# PotDiv2_v2.net
KiCad netlist of a schematic drawn in EAGLE
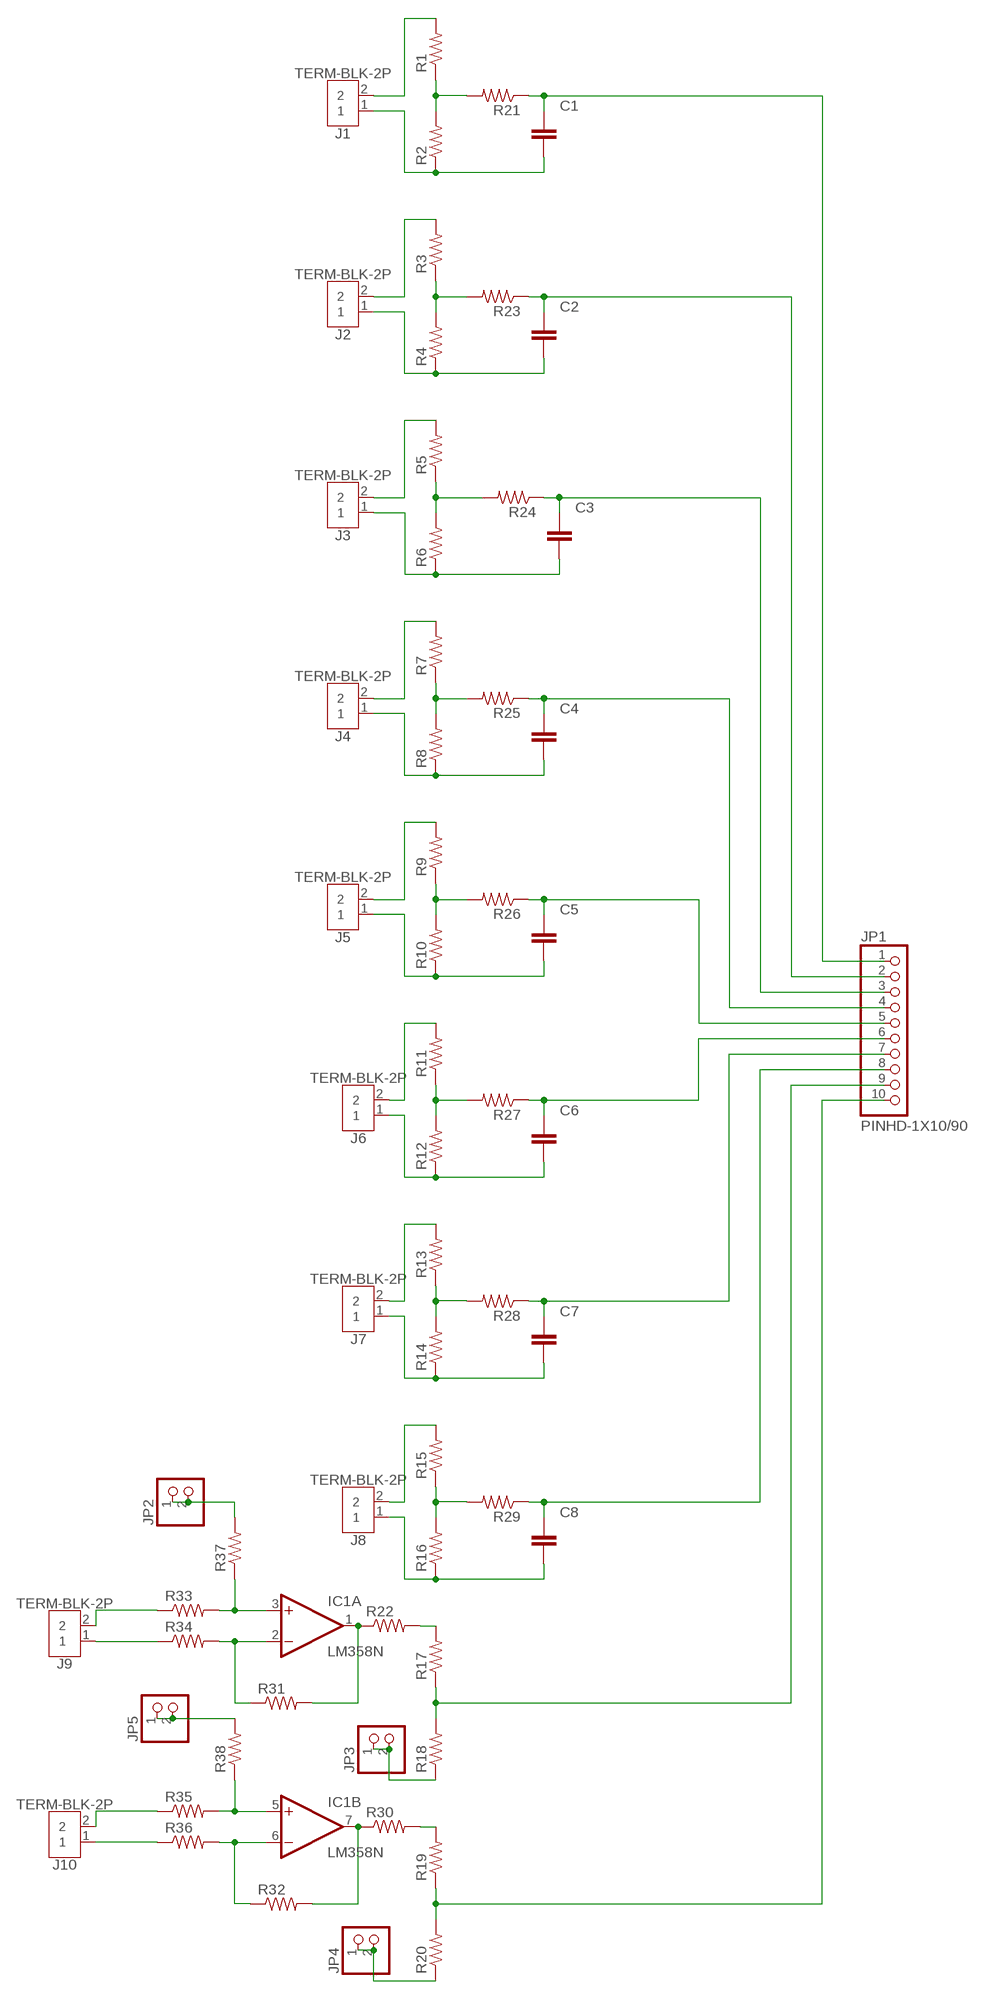
[diagram p0: schematic, sheet 1]

(export (version "E")
  (design (tool "Eeschema 10.0.6"))
  (components
    (comp (ref "C1")
      (value "C_RADIAL-12.5MM-DIA")
      (footprint "eagle-import:CAPRD550W60D1025H1250B")
      (libsource (lib "eagle-import") (part "CRADIAL-12.5MM-DIA_"))
    )
    (comp (ref "C2")
      (value "C_RADIAL-12.5MM-DIA")
      (footprint "eagle-import:CAPRD550W60D1025H1250B")
      (libsource (lib "eagle-import") (part "CRADIAL-12.5MM-DIA_"))
    )
    (comp (ref "C3")
      (value "C_RADIAL-12.5MM-DIA")
      (footprint "eagle-import:CAPRD550W60D1025H1250B")
      (libsource (lib "eagle-import") (part "CRADIAL-12.5MM-DIA_"))
    )
    (comp (ref "C4")
      (value "C_RADIAL-12.5MM-DIA")
      (footprint "eagle-import:CAPRD550W60D1025H1250B")
      (libsource (lib "eagle-import") (part "CRADIAL-12.5MM-DIA_"))
    )
    (comp (ref "C5")
      (value "C_RADIAL-12.5MM-DIA")
      (footprint "eagle-import:CAPRD550W60D1025H1250B")
      (libsource (lib "eagle-import") (part "CRADIAL-12.5MM-DIA_"))
    )
    (comp (ref "C6")
      (value "C_RADIAL-12.5MM-DIA")
      (footprint "eagle-import:CAPRD550W60D1025H1250B")
      (libsource (lib "eagle-import") (part "CRADIAL-12.5MM-DIA_"))
    )
    (comp (ref "C7")
      (value "C_RADIAL-12.5MM-DIA")
      (footprint "eagle-import:CAPRD550W60D1025H1250B")
      (libsource (lib "eagle-import") (part "CRADIAL-12.5MM-DIA_"))
    )
    (comp (ref "C8")
      (value "C_RADIAL-12.5MM-DIA")
      (footprint "eagle-import:CAPRD550W60D1025H1250B")
      (libsource (lib "eagle-import") (part "CRADIAL-12.5MM-DIA_"))
    )
    (comp (ref "IC1")
      (value "LM358N")
      (footprint "eagle-import:DIL08")
      (libsource (lib "eagle-import") (part "LM358N"))
    )
    (comp (ref "J1")
      (value "TERM-BLK-2P")
      (footprint "eagle-import:TERMBLK_508-2N")
      (fields (field (name "MANUFACTURER") "TE Connectivity AMP Connectors") (field (name "MPN") "282837-2"))
      (libsource (lib "eagle-import") (part "2828XX-2282837-2"))
    )
    (comp (ref "J2")
      (value "TERM-BLK-2P")
      (footprint "eagle-import:TERMBLK_508-2N")
      (fields (field (name "MANUFACTURER") "TE Connectivity AMP Connectors") (field (name "MPN") "282837-2"))
      (libsource (lib "eagle-import") (part "2828XX-2282837-2"))
    )
    (comp (ref "J3")
      (value "TERM-BLK-2P")
      (footprint "eagle-import:TERMBLK_508-2N")
      (fields (field (name "MANUFACTURER") "TE Connectivity AMP Connectors") (field (name "MPN") "282837-2"))
      (libsource (lib "eagle-import") (part "2828XX-2282837-2"))
    )
    (comp (ref "J4")
      (value "TERM-BLK-2P")
      (footprint "eagle-import:TERMBLK_508-2N")
      (fields (field (name "MANUFACTURER") "TE Connectivity AMP Connectors") (field (name "MPN") "282837-2"))
      (libsource (lib "eagle-import") (part "2828XX-2282837-2"))
    )
    (comp (ref "J5")
      (value "TERM-BLK-2P")
      (footprint "eagle-import:TERMBLK_508-2N")
      (fields (field (name "MANUFACTURER") "TE Connectivity AMP Connectors") (field (name "MPN") "282837-2"))
      (libsource (lib "eagle-import") (part "2828XX-2282837-2"))
    )
    (comp (ref "J6")
      (value "TERM-BLK-2P")
      (footprint "eagle-import:TERMBLK_508-2N")
      (fields (field (name "MANUFACTURER") "TE Connectivity AMP Connectors") (field (name "MPN") "282837-2"))
      (libsource (lib "eagle-import") (part "2828XX-2282837-2"))
    )
    (comp (ref "J7")
      (value "TERM-BLK-2P")
      (footprint "eagle-import:TERMBLK_508-2N")
      (fields (field (name "MANUFACTURER") "TE Connectivity AMP Connectors") (field (name "MPN") "282837-2"))
      (libsource (lib "eagle-import") (part "2828XX-2282837-2"))
    )
    (comp (ref "J8")
      (value "TERM-BLK-2P")
      (footprint "eagle-import:TERMBLK_508-2N")
      (fields (field (name "MANUFACTURER") "TE Connectivity AMP Connectors") (field (name "MPN") "282837-2"))
      (libsource (lib "eagle-import") (part "2828XX-2282837-2"))
    )
    (comp (ref "J9")
      (value "TERM-BLK-2P")
      (footprint "eagle-import:TERMBLK_508-2N")
      (fields (field (name "MANUFACTURER") "TE Connectivity AMP Connectors") (field (name "MPN") "282837-2"))
      (libsource (lib "eagle-import") (part "2828XX-2282837-2"))
    )
    (comp (ref "J10")
      (value "TERM-BLK-2P")
      (footprint "eagle-import:TERMBLK_508-2N")
      (fields (field (name "MANUFACTURER") "TE Connectivity AMP Connectors") (field (name "MPN") "282837-2"))
      (libsource (lib "eagle-import") (part "2828XX-2282837-2"))
    )
    (comp (ref "JP1")
      (value "PINHD-1X10/90")
      (footprint "eagle-import:1X10_90")
      (fields (field (name "MANUFACTURER") "Generic"))
      (libsource (lib "eagle-import") (part "PINHD-1X10/90"))
    )
    (comp (ref "JP2")
      (value "PINHD-1X2")
      (footprint "eagle-import:1X02")
      (libsource (lib "eagle-import") (part "PINHD-1X2"))
    )
    (comp (ref "JP3")
      (value "PINHD-1X2")
      (footprint "eagle-import:1X02")
      (libsource (lib "eagle-import") (part "PINHD-1X2"))
    )
    (comp (ref "JP4")
      (value "PINHD-1X2")
      (footprint "eagle-import:1X02")
      (libsource (lib "eagle-import") (part "PINHD-1X2"))
    )
    (comp (ref "JP5")
      (value "PINHD-1X2")
      (footprint "eagle-import:1X02")
      (libsource (lib "eagle-import") (part "PINHD-1X2"))
    )
    (comp (ref "R1")
      (value "R-US_AXIAL-7.2MM-PITCH")
      (footprint "eagle-import:RESAD724W46L381D178B")
      (libsource (lib "eagle-import") (part "R-USAXIAL-7.2MM-PITCH_"))
    )
    (comp (ref "R2")
      (value "R-US_AXIAL-7.2MM-PITCH")
      (footprint "eagle-import:RESAD724W46L381D178B")
      (libsource (lib "eagle-import") (part "R-USAXIAL-7.2MM-PITCH_"))
    )
    (comp (ref "R3")
      (value "R-US_AXIAL-7.2MM-PITCH")
      (footprint "eagle-import:RESAD724W46L381D178B")
      (libsource (lib "eagle-import") (part "R-USAXIAL-7.2MM-PITCH_"))
    )
    (comp (ref "R4")
      (value "R-US_AXIAL-7.2MM-PITCH")
      (footprint "eagle-import:RESAD724W46L381D178B")
      (libsource (lib "eagle-import") (part "R-USAXIAL-7.2MM-PITCH_"))
    )
    (comp (ref "R5")
      (value "R-US_AXIAL-7.2MM-PITCH")
      (footprint "eagle-import:RESAD724W46L381D178B")
      (libsource (lib "eagle-import") (part "R-USAXIAL-7.2MM-PITCH_"))
    )
    (comp (ref "R6")
      (value "R-US_AXIAL-7.2MM-PITCH")
      (footprint "eagle-import:RESAD724W46L381D178B")
      (libsource (lib "eagle-import") (part "R-USAXIAL-7.2MM-PITCH_"))
    )
    (comp (ref "R7")
      (value "R-US_AXIAL-7.2MM-PITCH")
      (footprint "eagle-import:RESAD724W46L381D178B")
      (libsource (lib "eagle-import") (part "R-USAXIAL-7.2MM-PITCH_"))
    )
    (comp (ref "R8")
      (value "R-US_AXIAL-7.2MM-PITCH")
      (footprint "eagle-import:RESAD724W46L381D178B")
      (libsource (lib "eagle-import") (part "R-USAXIAL-7.2MM-PITCH_"))
    )
    (comp (ref "R9")
      (value "R-US_AXIAL-7.2MM-PITCH")
      (footprint "eagle-import:RESAD724W46L381D178B")
      (libsource (lib "eagle-import") (part "R-USAXIAL-7.2MM-PITCH_"))
    )
    (comp (ref "R10")
      (value "R-US_AXIAL-7.2MM-PITCH")
      (footprint "eagle-import:RESAD724W46L381D178B")
      (libsource (lib "eagle-import") (part "R-USAXIAL-7.2MM-PITCH_"))
    )
    (comp (ref "R11")
      (value "R-US_AXIAL-7.2MM-PITCH")
      (footprint "eagle-import:RESAD724W46L381D178B")
      (libsource (lib "eagle-import") (part "R-USAXIAL-7.2MM-PITCH_"))
    )
    (comp (ref "R12")
      (value "R-US_AXIAL-7.2MM-PITCH")
      (footprint "eagle-import:RESAD724W46L381D178B")
      (libsource (lib "eagle-import") (part "R-USAXIAL-7.2MM-PITCH_"))
    )
    (comp (ref "R13")
      (value "R-US_AXIAL-7.2MM-PITCH")
      (footprint "eagle-import:RESAD724W46L381D178B")
      (libsource (lib "eagle-import") (part "R-USAXIAL-7.2MM-PITCH_"))
    )
    (comp (ref "R14")
      (value "R-US_AXIAL-7.2MM-PITCH")
      (footprint "eagle-import:RESAD724W46L381D178B")
      (libsource (lib "eagle-import") (part "R-USAXIAL-7.2MM-PITCH_"))
    )
    (comp (ref "R15")
      (value "R-US_AXIAL-7.2MM-PITCH")
      (footprint "eagle-import:RESAD724W46L381D178B")
      (libsource (lib "eagle-import") (part "R-USAXIAL-7.2MM-PITCH_"))
    )
    (comp (ref "R16")
      (value "R-US_AXIAL-7.2MM-PITCH")
      (footprint "eagle-import:RESAD724W46L381D178B")
      (libsource (lib "eagle-import") (part "R-USAXIAL-7.2MM-PITCH_"))
    )
    (comp (ref "R17")
      (value "R-US_AXIAL-7.2MM-PITCH")
      (footprint "eagle-import:RESAD724W46L381D178B")
      (libsource (lib "eagle-import") (part "R-USAXIAL-7.2MM-PITCH_"))
    )
    (comp (ref "R18")
      (value "R-US_AXIAL-7.2MM-PITCH")
      (footprint "eagle-import:RESAD724W46L381D178B")
      (libsource (lib "eagle-import") (part "R-USAXIAL-7.2MM-PITCH_"))
    )
    (comp (ref "R19")
      (value "R-US_AXIAL-7.2MM-PITCH")
      (footprint "eagle-import:RESAD724W46L381D178B")
      (libsource (lib "eagle-import") (part "R-USAXIAL-7.2MM-PITCH_"))
    )
    (comp (ref "R20")
      (value "R-US_AXIAL-7.2MM-PITCH")
      (footprint "eagle-import:RESAD724W46L381D178B")
      (libsource (lib "eagle-import") (part "R-USAXIAL-7.2MM-PITCH_"))
    )
    (comp (ref "R21")
      (value "R-US_AXIAL-7.2MM-PITCH")
      (footprint "eagle-import:RESAD724W46L381D178B")
      (libsource (lib "eagle-import") (part "R-USAXIAL-7.2MM-PITCH_"))
    )
    (comp (ref "R22")
      (value "R-US_AXIAL-7.2MM-PITCH")
      (footprint "eagle-import:RESAD724W46L381D178B")
      (libsource (lib "eagle-import") (part "R-USAXIAL-7.2MM-PITCH_"))
    )
    (comp (ref "R23")
      (value "R-US_AXIAL-7.2MM-PITCH")
      (footprint "eagle-import:RESAD724W46L381D178B")
      (libsource (lib "eagle-import") (part "R-USAXIAL-7.2MM-PITCH_"))
    )
    (comp (ref "R24")
      (value "R-US_AXIAL-7.2MM-PITCH")
      (footprint "eagle-import:RESAD724W46L381D178B")
      (libsource (lib "eagle-import") (part "R-USAXIAL-7.2MM-PITCH_"))
    )
    (comp (ref "R25")
      (value "R-US_AXIAL-7.2MM-PITCH")
      (footprint "eagle-import:RESAD724W46L381D178B")
      (libsource (lib "eagle-import") (part "R-USAXIAL-7.2MM-PITCH_"))
    )
    (comp (ref "R26")
      (value "R-US_AXIAL-7.2MM-PITCH")
      (footprint "eagle-import:RESAD724W46L381D178B")
      (libsource (lib "eagle-import") (part "R-USAXIAL-7.2MM-PITCH_"))
    )
    (comp (ref "R27")
      (value "R-US_AXIAL-7.2MM-PITCH")
      (footprint "eagle-import:RESAD724W46L381D178B")
      (libsource (lib "eagle-import") (part "R-USAXIAL-7.2MM-PITCH_"))
    )
    (comp (ref "R28")
      (value "R-US_AXIAL-7.2MM-PITCH")
      (footprint "eagle-import:RESAD724W46L381D178B")
      (libsource (lib "eagle-import") (part "R-USAXIAL-7.2MM-PITCH_"))
    )
    (comp (ref "R29")
      (value "R-US_AXIAL-7.2MM-PITCH")
      (footprint "eagle-import:RESAD724W46L381D178B")
      (libsource (lib "eagle-import") (part "R-USAXIAL-7.2MM-PITCH_"))
    )
    (comp (ref "R30")
      (value "R-US_AXIAL-7.2MM-PITCH")
      (footprint "eagle-import:RESAD724W46L381D178B")
      (libsource (lib "eagle-import") (part "R-USAXIAL-7.2MM-PITCH_"))
    )
    (comp (ref "R31")
      (value "R-US_AXIAL-7.2MM-PITCH")
      (footprint "eagle-import:RESAD724W46L381D178B")
      (libsource (lib "eagle-import") (part "R-USAXIAL-7.2MM-PITCH_"))
    )
    (comp (ref "R32")
      (value "R-US_AXIAL-7.2MM-PITCH")
      (footprint "eagle-import:RESAD724W46L381D178B")
      (libsource (lib "eagle-import") (part "R-USAXIAL-7.2MM-PITCH_"))
    )
    (comp (ref "R33")
      (value "R-US_AXIAL-7.2MM-PITCH")
      (footprint "eagle-import:RESAD724W46L381D178B")
      (libsource (lib "eagle-import") (part "R-USAXIAL-7.2MM-PITCH_"))
    )
    (comp (ref "R34")
      (value "R-US_AXIAL-7.2MM-PITCH")
      (footprint "eagle-import:RESAD724W46L381D178B")
      (libsource (lib "eagle-import") (part "R-USAXIAL-7.2MM-PITCH_"))
    )
    (comp (ref "R35")
      (value "R-US_AXIAL-7.2MM-PITCH")
      (footprint "eagle-import:RESAD724W46L381D178B")
      (libsource (lib "eagle-import") (part "R-USAXIAL-7.2MM-PITCH_"))
    )
    (comp (ref "R36")
      (value "R-US_AXIAL-7.2MM-PITCH")
      (footprint "eagle-import:RESAD724W46L381D178B")
      (libsource (lib "eagle-import") (part "R-USAXIAL-7.2MM-PITCH_"))
    )
    (comp (ref "R37")
      (value "R-US_AXIAL-7.2MM-PITCH")
      (footprint "eagle-import:RESAD724W46L381D178B")
      (libsource (lib "eagle-import") (part "R-USAXIAL-7.2MM-PITCH_"))
    )
    (comp (ref "R38")
      (value "R-US_AXIAL-7.2MM-PITCH")
      (footprint "eagle-import:RESAD724W46L381D178B")
      (libsource (lib "eagle-import") (part "R-USAXIAL-7.2MM-PITCH_"))
    )
  )
  (nets
    (net (code "1") (name "Net-(C1-Pad1)") (class "Default")
      (node (ref "C1") (pin "1") (pinfunction "1_1") (pintype "passive"))
      (node (ref "JP1") (pin "1") (pinfunction "1_1") (pintype "passive"))
      (node (ref "R21") (pin "1") (pinfunction "1_1") (pintype "passive"))
    )
    (net (code "2") (name "Net-(C1-Pad2)") (class "Default")
      (node (ref "C1") (pin "2") (pinfunction "2_2") (pintype "passive"))
      (node (ref "J1") (pin "1") (pinfunction "1_1") (pintype "bidirectional"))
      (node (ref "R2") (pin "1") (pinfunction "1_1") (pintype "passive"))
    )
    (net (code "3") (name "Net-(C2-Pad1)") (class "Default")
      (node (ref "C2") (pin "1") (pinfunction "1_1") (pintype "passive"))
      (node (ref "JP1") (pin "2") (pinfunction "2_2") (pintype "passive"))
      (node (ref "R23") (pin "1") (pinfunction "1_1") (pintype "passive"))
    )
    (net (code "4") (name "Net-(C2-Pad2)") (class "Default")
      (node (ref "C2") (pin "2") (pinfunction "2_2") (pintype "passive"))
      (node (ref "J2") (pin "1") (pinfunction "1_1") (pintype "bidirectional"))
      (node (ref "R4") (pin "1") (pinfunction "1_1") (pintype "passive"))
    )
    (net (code "5") (name "Net-(C3-Pad1)") (class "Default")
      (node (ref "C3") (pin "1") (pinfunction "1_1") (pintype "passive"))
      (node (ref "JP1") (pin "3") (pinfunction "3_3") (pintype "passive"))
      (node (ref "R24") (pin "1") (pinfunction "1_1") (pintype "passive"))
    )
    (net (code "6") (name "Net-(C3-Pad2)") (class "Default")
      (node (ref "C3") (pin "2") (pinfunction "2_2") (pintype "passive"))
      (node (ref "J3") (pin "1") (pinfunction "1_1") (pintype "bidirectional"))
      (node (ref "R6") (pin "1") (pinfunction "1_1") (pintype "passive"))
    )
    (net (code "7") (name "Net-(C4-Pad1)") (class "Default")
      (node (ref "C4") (pin "1") (pinfunction "1_1") (pintype "passive"))
      (node (ref "JP1") (pin "4") (pinfunction "4_4") (pintype "passive"))
      (node (ref "R25") (pin "1") (pinfunction "1_1") (pintype "passive"))
    )
    (net (code "8") (name "Net-(C4-Pad2)") (class "Default")
      (node (ref "C4") (pin "2") (pinfunction "2_2") (pintype "passive"))
      (node (ref "J4") (pin "1") (pinfunction "1_1") (pintype "bidirectional"))
      (node (ref "R8") (pin "1") (pinfunction "1_1") (pintype "passive"))
    )
    (net (code "9") (name "Net-(C5-Pad1)") (class "Default")
      (node (ref "C5") (pin "1") (pinfunction "1_1") (pintype "passive"))
      (node (ref "JP1") (pin "5") (pinfunction "5_5") (pintype "passive"))
      (node (ref "R26") (pin "1") (pinfunction "1_1") (pintype "passive"))
    )
    (net (code "10") (name "Net-(C5-Pad2)") (class "Default")
      (node (ref "C5") (pin "2") (pinfunction "2_2") (pintype "passive"))
      (node (ref "J5") (pin "1") (pinfunction "1_1") (pintype "bidirectional"))
      (node (ref "R10") (pin "1") (pinfunction "1_1") (pintype "passive"))
    )
    (net (code "11") (name "Net-(C6-Pad1)") (class "Default")
      (node (ref "C6") (pin "1") (pinfunction "1_1") (pintype "passive"))
      (node (ref "JP1") (pin "6") (pinfunction "6_6") (pintype "passive"))
      (node (ref "R27") (pin "1") (pinfunction "1_1") (pintype "passive"))
    )
    (net (code "12") (name "Net-(C6-Pad2)") (class "Default")
      (node (ref "C6") (pin "2") (pinfunction "2_2") (pintype "passive"))
      (node (ref "J6") (pin "1") (pinfunction "1_1") (pintype "bidirectional"))
      (node (ref "R12") (pin "1") (pinfunction "1_1") (pintype "passive"))
    )
    (net (code "13") (name "Net-(C7-Pad1)") (class "Default")
      (node (ref "C7") (pin "1") (pinfunction "1_1") (pintype "passive"))
      (node (ref "JP1") (pin "7") (pinfunction "7_7") (pintype "passive"))
      (node (ref "R28") (pin "1") (pinfunction "1_1") (pintype "passive"))
    )
    (net (code "14") (name "Net-(C7-Pad2)") (class "Default")
      (node (ref "C7") (pin "2") (pinfunction "2_2") (pintype "passive"))
      (node (ref "J7") (pin "1") (pinfunction "1_1") (pintype "bidirectional"))
      (node (ref "R14") (pin "1") (pinfunction "1_1") (pintype "passive"))
    )
    (net (code "15") (name "Net-(C8-Pad1)") (class "Default")
      (node (ref "C8") (pin "1") (pinfunction "1_1") (pintype "passive"))
      (node (ref "JP1") (pin "8") (pinfunction "8_8") (pintype "passive"))
      (node (ref "R29") (pin "1") (pinfunction "1_1") (pintype "passive"))
    )
    (net (code "16") (name "Net-(C8-Pad2)") (class "Default")
      (node (ref "C8") (pin "2") (pinfunction "2_2") (pintype "passive"))
      (node (ref "J8") (pin "1") (pinfunction "1_1") (pintype "bidirectional"))
      (node (ref "R16") (pin "1") (pinfunction "1_1") (pintype "passive"))
    )
    (net (code "17") (name "Net-(IC1A-+IN)") (class "Default")
      (node (ref "IC1") (pin "3") (pinfunction "+IN_3") (pintype "input"))
      (node (ref "R33") (pin "2") (pinfunction "2_2") (pintype "passive"))
      (node (ref "R37") (pin "1") (pinfunction "1_1") (pintype "passive"))
    )
    (net (code "18") (name "Net-(IC1A--IN)") (class "Default")
      (node (ref "IC1") (pin "2") (pinfunction "-IN_2") (pintype "input"))
      (node (ref "R31") (pin "1") (pinfunction "1_1") (pintype "passive"))
      (node (ref "R34") (pin "2") (pinfunction "2_2") (pintype "passive"))
    )
    (net (code "19") (name "Net-(IC1A-OUT)") (class "Default")
      (node (ref "IC1") (pin "1") (pinfunction "OUT_1") (pintype "output"))
      (node (ref "R22") (pin "1") (pinfunction "1_1") (pintype "passive"))
      (node (ref "R31") (pin "2") (pinfunction "2_2") (pintype "passive"))
    )
    (net (code "20") (name "Net-(IC1B-+IN)") (class "Default")
      (node (ref "IC1") (pin "5") (pinfunction "+IN_5") (pintype "input"))
      (node (ref "R35") (pin "2") (pinfunction "2_2") (pintype "passive"))
      (node (ref "R38") (pin "1") (pinfunction "1_1") (pintype "passive"))
    )
    (net (code "21") (name "Net-(IC1B--IN)") (class "Default")
      (node (ref "IC1") (pin "6") (pinfunction "-IN_6") (pintype "input"))
      (node (ref "R32") (pin "1") (pinfunction "1_1") (pintype "passive"))
      (node (ref "R36") (pin "2") (pinfunction "2_2") (pintype "passive"))
    )
    (net (code "22") (name "Net-(IC1B-OUT)") (class "Default")
      (node (ref "IC1") (pin "7") (pinfunction "OUT_7") (pintype "output"))
      (node (ref "R30") (pin "1") (pinfunction "1_1") (pintype "passive"))
      (node (ref "R32") (pin "2") (pinfunction "2_2") (pintype "passive"))
    )
    (net (code "23") (name "Net-(J1-Pad2)") (class "Default")
      (node (ref "J1") (pin "2") (pinfunction "2_2") (pintype "bidirectional"))
      (node (ref "R1") (pin "2") (pinfunction "2_2") (pintype "passive"))
    )
    (net (code "24") (name "Net-(J2-Pad2)") (class "Default")
      (node (ref "J2") (pin "2") (pinfunction "2_2") (pintype "bidirectional"))
      (node (ref "R3") (pin "2") (pinfunction "2_2") (pintype "passive"))
    )
    (net (code "25") (name "Net-(J3-Pad2)") (class "Default")
      (node (ref "J3") (pin "2") (pinfunction "2_2") (pintype "bidirectional"))
      (node (ref "R5") (pin "2") (pinfunction "2_2") (pintype "passive"))
    )
    (net (code "26") (name "Net-(J4-Pad2)") (class "Default")
      (node (ref "J4") (pin "2") (pinfunction "2_2") (pintype "bidirectional"))
      (node (ref "R7") (pin "2") (pinfunction "2_2") (pintype "passive"))
    )
    (net (code "27") (name "Net-(J5-Pad2)") (class "Default")
      (node (ref "J5") (pin "2") (pinfunction "2_2") (pintype "bidirectional"))
      (node (ref "R9") (pin "2") (pinfunction "2_2") (pintype "passive"))
    )
    (net (code "28") (name "Net-(J6-Pad2)") (class "Default")
      (node (ref "J6") (pin "2") (pinfunction "2_2") (pintype "bidirectional"))
      (node (ref "R11") (pin "2") (pinfunction "2_2") (pintype "passive"))
    )
    (net (code "29") (name "Net-(J7-Pad2)") (class "Default")
      (node (ref "J7") (pin "2") (pinfunction "2_2") (pintype "bidirectional"))
      (node (ref "R13") (pin "2") (pinfunction "2_2") (pintype "passive"))
    )
    (net (code "30") (name "Net-(J8-Pad2)") (class "Default")
      (node (ref "J8") (pin "2") (pinfunction "2_2") (pintype "bidirectional"))
      (node (ref "R15") (pin "2") (pinfunction "2_2") (pintype "passive"))
    )
    (net (code "31") (name "Net-(J9-Pad1)") (class "Default")
      (node (ref "J9") (pin "1") (pinfunction "1_1") (pintype "bidirectional"))
      (node (ref "R34") (pin "1") (pinfunction "1_1") (pintype "passive"))
    )
    (net (code "32") (name "Net-(J9-Pad2)") (class "Default")
      (node (ref "J9") (pin "2") (pinfunction "2_2") (pintype "bidirectional"))
      (node (ref "R33") (pin "1") (pinfunction "1_1") (pintype "passive"))
    )
    (net (code "33") (name "Net-(J10-Pad1)") (class "Default")
      (node (ref "J10") (pin "1") (pinfunction "1_1") (pintype "bidirectional"))
      (node (ref "R36") (pin "1") (pinfunction "1_1") (pintype "passive"))
    )
    (net (code "34") (name "Net-(J10-Pad2)") (class "Default")
      (node (ref "J10") (pin "2") (pinfunction "2_2") (pintype "bidirectional"))
      (node (ref "R35") (pin "1") (pinfunction "1_1") (pintype "passive"))
    )
    (net (code "35") (name "Net-(JP1-Pad9)") (class "Default")
      (node (ref "JP1") (pin "9") (pinfunction "9_9") (pintype "passive"))
      (node (ref "R17") (pin "1") (pinfunction "1_1") (pintype "passive"))
      (node (ref "R18") (pin "2") (pinfunction "2_2") (pintype "passive"))
    )
    (net (code "36") (name "Net-(JP1-Pad10)") (class "Default")
      (node (ref "JP1") (pin "10") (pinfunction "10_10") (pintype "passive"))
      (node (ref "R19") (pin "1") (pinfunction "1_1") (pintype "passive"))
      (node (ref "R20") (pin "2") (pinfunction "2_2") (pintype "passive"))
    )
    (net (code "37") (name "Net-(JP2-Pad1)") (class "Default")
      (node (ref "JP2") (pin "1") (pinfunction "1_1") (pintype "passive"))
      (node (ref "JP2") (pin "2") (pinfunction "2_2") (pintype "passive"))
      (node (ref "R37") (pin "2") (pinfunction "2_2") (pintype "passive"))
    )
    (net (code "38") (name "Net-(JP3-Pad1)") (class "Default")
      (node (ref "JP3") (pin "1") (pinfunction "1_1") (pintype "passive"))
      (node (ref "JP3") (pin "2") (pinfunction "2_2") (pintype "passive"))
      (node (ref "R18") (pin "1") (pinfunction "1_1") (pintype "passive"))
    )
    (net (code "39") (name "Net-(JP4-Pad1)") (class "Default")
      (node (ref "JP4") (pin "1") (pinfunction "1_1") (pintype "passive"))
      (node (ref "JP4") (pin "2") (pinfunction "2_2") (pintype "passive"))
      (node (ref "R20") (pin "1") (pinfunction "1_1") (pintype "passive"))
    )
    (net (code "40") (name "Net-(JP5-Pad1)") (class "Default")
      (node (ref "JP5") (pin "1") (pinfunction "1_1") (pintype "passive"))
      (node (ref "JP5") (pin "2") (pinfunction "2_2") (pintype "passive"))
      (node (ref "R38") (pin "2") (pinfunction "2_2") (pintype "passive"))
    )
    (net (code "41") (name "Net-(R1-Pad1)") (class "Default")
      (node (ref "R1") (pin "1") (pinfunction "1_1") (pintype "passive"))
      (node (ref "R2") (pin "2") (pinfunction "2_2") (pintype "passive"))
      (node (ref "R21") (pin "2") (pinfunction "2_2") (pintype "passive"))
    )
    (net (code "42") (name "Net-(R10-Pad2)") (class "Default")
      (node (ref "R10") (pin "2") (pinfunction "2_2") (pintype "passive"))
      (node (ref "R26") (pin "2") (pinfunction "2_2") (pintype "passive"))
      (node (ref "R9") (pin "1") (pinfunction "1_1") (pintype "passive"))
    )
    (net (code "43") (name "Net-(R11-Pad1)") (class "Default")
      (node (ref "R11") (pin "1") (pinfunction "1_1") (pintype "passive"))
      (node (ref "R12") (pin "2") (pinfunction "2_2") (pintype "passive"))
      (node (ref "R27") (pin "2") (pinfunction "2_2") (pintype "passive"))
    )
    (net (code "44") (name "Net-(R13-Pad1)") (class "Default")
      (node (ref "R13") (pin "1") (pinfunction "1_1") (pintype "passive"))
      (node (ref "R14") (pin "2") (pinfunction "2_2") (pintype "passive"))
      (node (ref "R28") (pin "2") (pinfunction "2_2") (pintype "passive"))
    )
    (net (code "45") (name "Net-(R15-Pad1)") (class "Default")
      (node (ref "R15") (pin "1") (pinfunction "1_1") (pintype "passive"))
      (node (ref "R16") (pin "2") (pinfunction "2_2") (pintype "passive"))
      (node (ref "R29") (pin "2") (pinfunction "2_2") (pintype "passive"))
    )
    (net (code "46") (name "Net-(R17-Pad2)") (class "Default")
      (node (ref "R17") (pin "2") (pinfunction "2_2") (pintype "passive"))
      (node (ref "R22") (pin "2") (pinfunction "2_2") (pintype "passive"))
    )
    (net (code "47") (name "Net-(R19-Pad2)") (class "Default")
      (node (ref "R19") (pin "2") (pinfunction "2_2") (pintype "passive"))
      (node (ref "R30") (pin "2") (pinfunction "2_2") (pintype "passive"))
    )
    (net (code "48") (name "Net-(R23-Pad2)") (class "Default")
      (node (ref "R23") (pin "2") (pinfunction "2_2") (pintype "passive"))
      (node (ref "R3") (pin "1") (pinfunction "1_1") (pintype "passive"))
      (node (ref "R4") (pin "2") (pinfunction "2_2") (pintype "passive"))
    )
    (net (code "49") (name "Net-(R24-Pad2)") (class "Default")
      (node (ref "R24") (pin "2") (pinfunction "2_2") (pintype "passive"))
      (node (ref "R5") (pin "1") (pinfunction "1_1") (pintype "passive"))
      (node (ref "R6") (pin "2") (pinfunction "2_2") (pintype "passive"))
    )
    (net (code "50") (name "Net-(R25-Pad2)") (class "Default")
      (node (ref "R25") (pin "2") (pinfunction "2_2") (pintype "passive"))
      (node (ref "R7") (pin "1") (pinfunction "1_1") (pintype "passive"))
      (node (ref "R8") (pin "2") (pinfunction "2_2") (pintype "passive"))
    )
  )
)
